# ETH_PHY_IC.net
KiCad netlist of a schematic drawn in Altium Designer
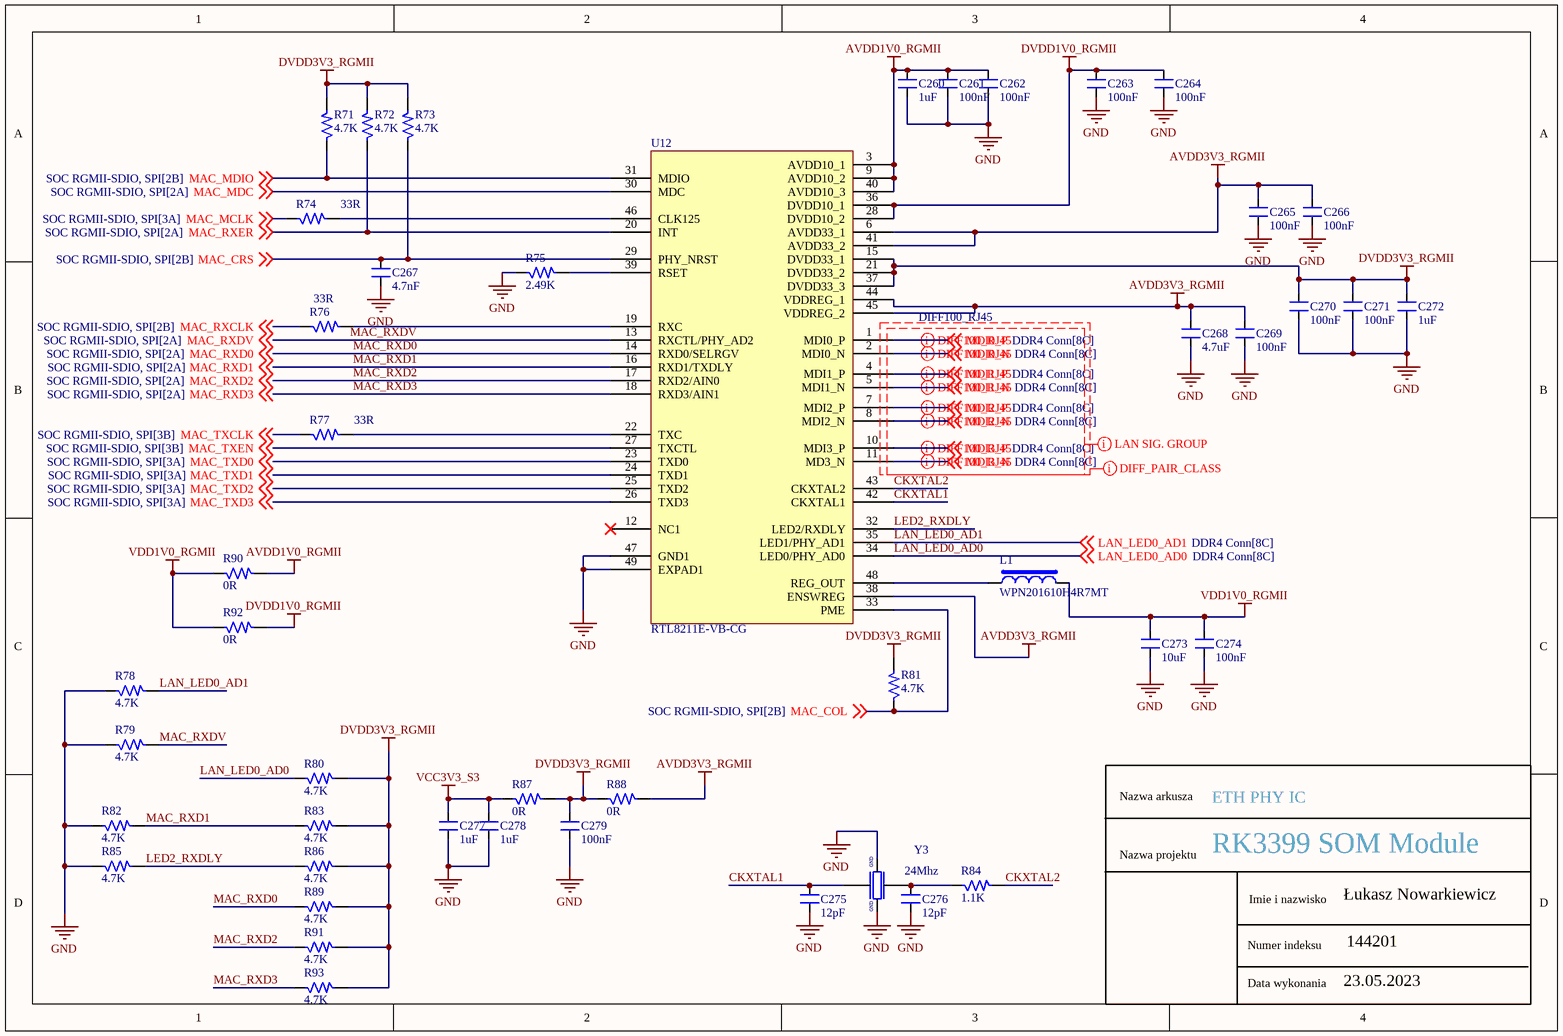
[diagram p0: ETH PHY IC.SchDoc]

(export (version "E")
  (design (tool "Eeschema 10.0.6"))
  (components
    (comp (ref "C260")
      (value "1uF")
      (footprint "CAP_0201")
      (description "1µF ±20% 16V Ceramic Capacitor X5R 0201 (0603 Metric)")
      (fields
        (field (name "MANUFACTURER") "Samsung Electro-Mechanics")
        (field (name "MANUFACTURER PART NUMBER") "CL03A105MO3NRNH")
      )
      (libsource (lib "EsteemPCB_SOM_Course_intlib") (part "CAP_1uF-16V-10%-0201"))
    )
    (comp (ref "C261")
      (value "100nF")
      (footprint "CAP_0201")
      (description "0.1µF ±10% 25V Ceramic Capacitor X5R 0201 (0603 Metric)")
      (fields
        (field (name "MANUFACTURER") "TDK Corporation")
        (field (name "MANUFACTURER PART NUMBER") "C0603X5R1E104K030BB")
      )
      (libsource (lib "EsteemPCB_SOM_Course_intlib") (part "CAP_100nF-25V-10%-0201"))
    )
    (comp (ref "C262")
      (value "100nF")
      (footprint "CAP_0201")
      (description "0.1µF ±10% 25V Ceramic Capacitor X5R 0201 (0603 Metric)")
      (fields
        (field (name "MANUFACTURER") "TDK Corporation")
        (field (name "MANUFACTURER PART NUMBER") "C0603X5R1E104K030BB")
      )
      (libsource (lib "EsteemPCB_SOM_Course_intlib") (part "CAP_100nF-25V-10%-0201"))
    )
    (comp (ref "C263")
      (value "100nF")
      (footprint "CAP_0201")
      (description "0.1µF ±10% 25V Ceramic Capacitor X5R 0201 (0603 Metric)")
      (fields
        (field (name "MANUFACTURER") "TDK Corporation")
        (field (name "MANUFACTURER PART NUMBER") "C0603X5R1E104K030BB")
      )
      (libsource (lib "EsteemPCB_SOM_Course_intlib") (part "CAP_100nF-25V-10%-0201"))
    )
    (comp (ref "C264")
      (value "100nF")
      (footprint "CAP_0201")
      (description "0.1µF ±10% 25V Ceramic Capacitor X5R 0201 (0603 Metric)")
      (fields
        (field (name "MANUFACTURER") "TDK Corporation")
        (field (name "MANUFACTURER PART NUMBER") "C0603X5R1E104K030BB")
      )
      (libsource (lib "EsteemPCB_SOM_Course_intlib") (part "CAP_100nF-25V-10%-0201"))
    )
    (comp (ref "C265")
      (value "100nF")
      (footprint "CAP_0201")
      (description "0.1µF ±10% 25V Ceramic Capacitor X5R 0201 (0603 Metric)")
      (fields
        (field (name "MANUFACTURER") "TDK Corporation")
        (field (name "MANUFACTURER PART NUMBER") "C0603X5R1E104K030BB")
      )
      (libsource (lib "EsteemPCB_SOM_Course_intlib") (part "CAP_100nF-25V-10%-0201"))
    )
    (comp (ref "C266")
      (value "100nF")
      (footprint "CAP_0201")
      (description "0.1µF ±10% 25V Ceramic Capacitor X5R 0201 (0603 Metric)")
      (fields
        (field (name "MANUFACTURER") "TDK Corporation")
        (field (name "MANUFACTURER PART NUMBER") "C0603X5R1E104K030BB")
      )
      (libsource (lib "EsteemPCB_SOM_Course_intlib") (part "CAP_100nF-25V-10%-0201"))
    )
    (comp (ref "C267")
      (value "4.7nF")
      (footprint "CAP_0201")
      (description "4700pF ±10% 10V Ceramic Capacitor X7R 0201 (0603 Metric)")
      (fields
        (field (name "MANUFACTURER") "AVX Corporation")
        (field (name "MANUFACTURER PART NUMBER") "0201ZC472KAT2A")
      )
      (libsource (lib "EsteemPCB_SOM_Course_intlib") (part "CAP_4.7nF-10V-10%-0201"))
    )
    (comp (ref "C268")
      (value "4.7uF")
      (footprint "CAP_0201")
      (description "4.7µF ±20% 6.3V Ceramic Capacitor X5R 0201 (0603 Metric)")
      (fields
        (field (name "MANUFACTURER") "Murata Electronics")
        (field (name "MANUFACTURER PART NUMBER") "GRM035R60J475ME15D")
      )
      (libsource (lib "EsteemPCB_SOM_Course_intlib") (part "CAP_4.7uF-6.3V-20%-0201"))
    )
    (comp (ref "C269")
      (value "100nF")
      (footprint "CAP_0201")
      (description "0.1µF ±10% 25V Ceramic Capacitor X5R 0201 (0603 Metric)")
      (fields
        (field (name "MANUFACTURER") "TDK Corporation")
        (field (name "MANUFACTURER PART NUMBER") "C0603X5R1E104K030BB")
      )
      (libsource (lib "EsteemPCB_SOM_Course_intlib") (part "CAP_100nF-25V-10%-0201"))
    )
    (comp (ref "C270")
      (value "100nF")
      (footprint "CAP_0201")
      (description "0.1µF ±10% 25V Ceramic Capacitor X5R 0201 (0603 Metric)")
      (fields
        (field (name "MANUFACTURER") "TDK Corporation")
        (field (name "MANUFACTURER PART NUMBER") "C0603X5R1E104K030BB")
      )
      (libsource (lib "EsteemPCB_SOM_Course_intlib") (part "CAP_100nF-25V-10%-0201"))
    )
    (comp (ref "C271")
      (value "100nF")
      (footprint "CAP_0201")
      (description "0.1µF ±10% 25V Ceramic Capacitor X5R 0201 (0603 Metric)")
      (fields
        (field (name "MANUFACTURER") "TDK Corporation")
        (field (name "MANUFACTURER PART NUMBER") "C0603X5R1E104K030BB")
      )
      (libsource (lib "EsteemPCB_SOM_Course_intlib") (part "CAP_100nF-25V-10%-0201"))
    )
    (comp (ref "C272")
      (value "1uF")
      (footprint "CAP_0603")
      (description "1µF ±10% 10V Ceramic Capacitor X5R 0603 (1608 Metric)")
      (fields
        (field (name "MANUFACTURER") "Samsung Electro-Mechanics")
        (field (name "MANUFACTURER PART NUMBER") "CL10A105KP8NNNC")
      )
      (libsource (lib "RK3399 _Module_Schlib") (part "CAP_1uF-10V-5%-0603"))
    )
    (comp (ref "C273")
      (value "10uF")
      (footprint "CAP_0402")
      (description "10µF ±20% 10V Ceramic Capacitor X5R 0402 (1005 Metric)")
      (fields
        (field (name "MANUFACTURER PART NUMBER") "CL05A106MP5NUNC")
        (field (name "MANUFACTURER") "Samsung Electro-Mechanics")
      )
      (libsource (lib "EsteemPCB_SOM_Course_intlib") (part "CAP_10uF-10V-20%-0402"))
    )
    (comp (ref "C274")
      (value "100nF")
      (footprint "CAP_0201")
      (description "0.1µF ±10% 25V Ceramic Capacitor X5R 0201 (0603 Metric)")
      (fields
        (field (name "MANUFACTURER") "TDK Corporation")
        (field (name "MANUFACTURER PART NUMBER") "C0603X5R1E104K030BB")
      )
      (libsource (lib "EsteemPCB_SOM_Course_intlib") (part "CAP_100nF-25V-10%-0201"))
    )
    (comp (ref "C275")
      (value "12pF")
      (footprint "CAP_0201")
      (description "12pF ±10% 16V Ceramic Capacitor C0G, NP0 0201 (0603 Metric)")
      (fields
        (field (name "MANUFACTURER") "AVX Corporation")
        (field (name "MANUFACTURER PART NUMBER") "0201YA120KAT2A")
      )
      (libsource (lib "EsteemPCB_SOM_Course_intlib") (part "CAP_12pF-16V-10%-0201"))
    )
    (comp (ref "C276")
      (value "12pF")
      (footprint "CAP_0201")
      (description "12pF ±10% 16V Ceramic Capacitor C0G, NP0 0201 (0603 Metric)")
      (fields
        (field (name "MANUFACTURER") "AVX Corporation")
        (field (name "MANUFACTURER PART NUMBER") "0201YA120KAT2A")
      )
      (libsource (lib "EsteemPCB_SOM_Course_intlib") (part "CAP_12pF-16V-10%-0201"))
    )
    (comp (ref "C277")
      (value "1uF")
      (footprint "CAP_0201")
      (description "1µF ±20% 16V Ceramic Capacitor X5R 0201 (0603 Metric)")
      (fields
        (field (name "MANUFACTURER") "Samsung Electro-Mechanics")
        (field (name "MANUFACTURER PART NUMBER") "CL03A105MO3NRNH")
      )
      (libsource (lib "EsteemPCB_SOM_Course_intlib") (part "CAP_1uF-16V-10%-0201"))
    )
    (comp (ref "C278")
      (value "1uF")
      (footprint "CAP_0201")
      (description "1µF ±20% 16V Ceramic Capacitor X5R 0201 (0603 Metric)")
      (fields
        (field (name "MANUFACTURER") "Samsung Electro-Mechanics")
        (field (name "MANUFACTURER PART NUMBER") "CL03A105MO3NRNH")
      )
      (libsource (lib "EsteemPCB_SOM_Course_intlib") (part "CAP_1uF-16V-10%-0201"))
    )
    (comp (ref "C279")
      (value "100nF")
      (footprint "CAP_0201")
      (description "0.1µF ±10% 25V Ceramic Capacitor X5R 0201 (0603 Metric)")
      (fields
        (field (name "MANUFACTURER") "TDK Corporation")
        (field (name "MANUFACTURER PART NUMBER") "C0603X5R1E104K030BB")
      )
      (libsource (lib "EsteemPCB_SOM_Course_intlib") (part "CAP_100nF-25V-10%-0201"))
    )
    (comp (ref "L1")
      (value "WPN201610H4R7MT")
      (footprint "IND_62.9_110X86.6_SMD")
      (description "4.7uH ±20% 900mA 425mΩ SMD,2.0x1.6x1.0mm Power Inductors RoHS")
      (fields (field (name "MANUFACTURER") "Sunlord"))
      (libsource (lib "RK3399 _Module_Schlib") (part "IND_4.7uH-0.9A-20%-SMD"))
    )
    (comp (ref "R71")
      (value "4.7K")
      (footprint "RES_0201")
      (description "4.02 kOhms ±1% 0.05W, 1/20W Chip Resistor 0201 (0603 Metric) Thick Film")
      (fields
        (field (name "MANUFACTURER") "Yageo")
        (field (name "MANUFACTURER PART NUMBER") "RC0201FR-074K02L")
      )
      (libsource (lib "EsteemPCB_SOM_Course_intlib") (part "RES_4.7K-0.1W-1%-0201"))
    )
    (comp (ref "R72")
      (value "4.7K")
      (footprint "RES_0201")
      (description "4.02 kOhms ±1% 0.05W, 1/20W Chip Resistor 0201 (0603 Metric) Thick Film")
      (fields
        (field (name "MANUFACTURER") "Yageo")
        (field (name "MANUFACTURER PART NUMBER") "RC0201FR-074K02L")
      )
      (libsource (lib "EsteemPCB_SOM_Course_intlib") (part "RES_4.7K-0.1W-1%-0201"))
    )
    (comp (ref "R73")
      (value "4.7K")
      (footprint "RES_0201")
      (description "4.02 kOhms ±1% 0.05W, 1/20W Chip Resistor 0201 (0603 Metric) Thick Film")
      (fields
        (field (name "MANUFACTURER") "Yageo")
        (field (name "MANUFACTURER PART NUMBER") "RC0201FR-074K02L")
      )
      (libsource (lib "EsteemPCB_SOM_Course_intlib") (part "RES_4.7K-0.1W-1%-0201"))
    )
    (comp (ref "R74")
      (value "33R")
      (footprint "RES_0201")
      (description "33 Ohms ±1% 0.05W, 1/20W Chip Resistor 0201 (0603 Metric) Thick Film")
      (fields
        (field (name "MANUFACTURER") "Yageo")
        (field (name "MANUFACTURER PART NUMBER") "RC0201FR-0733RL")
      )
      (libsource (lib "EsteemPCB_SOM_Course_intlib") (part "RES_33R-0.05W-1%-0201"))
    )
    (comp (ref "R75")
      (value "2.49K")
      (footprint "RES_0201")
      (description "2.49 kOhms ±1% 0.05W, 1/20W Chip Resistor 0201 (0603 Metric) Automotive AEC-Q200 Thick Film")
      (fields
        (field (name "MANUFACTURER") "Panasonic Electronic Components")
        (field (name "MANUFACTURER PART NUMBER") "ERJ-1GNF2491C")
      )
      (libsource (lib "EsteemPCB_SOM_Course_intlib") (part "RES_2.49K-0.05W-1%-0201"))
    )
    (comp (ref "R76")
      (value "33R")
      (footprint "RES_0201")
      (description "33 Ohms ±1% 0.05W, 1/20W Chip Resistor 0201 (0603 Metric) Thick Film")
      (fields
        (field (name "MANUFACTURER") "Yageo")
        (field (name "MANUFACTURER PART NUMBER") "RC0201FR-0733RL")
      )
      (libsource (lib "EsteemPCB_SOM_Course_intlib") (part "RES_33R-0.05W-1%-0201"))
    )
    (comp (ref "R77")
      (value "33R")
      (footprint "RES_0201")
      (description "33 Ohms ±1% 0.05W, 1/20W Chip Resistor 0201 (0603 Metric) Thick Film")
      (fields
        (field (name "MANUFACTURER") "Yageo")
        (field (name "MANUFACTURER PART NUMBER") "RC0201FR-0733RL")
      )
      (libsource (lib "EsteemPCB_SOM_Course_intlib") (part "RES_33R-0.05W-1%-0201"))
    )
    (comp (ref "R78")
      (value "4.7K")
      (footprint "RES_0201")
      (description "4.02 kOhms ±1% 0.05W, 1/20W Chip Resistor 0201 (0603 Metric) Thick Film")
      (fields
        (field (name "MANUFACTURER") "Yageo")
        (field (name "MANUFACTURER PART NUMBER") "RC0201FR-074K02L")
      )
      (libsource (lib "EsteemPCB_SOM_Course_intlib") (part "RES_4.7K-0.1W-1%-0201"))
    )
    (comp (ref "R79")
      (value "4.7K")
      (footprint "RES_0201")
      (description "4.02 kOhms ±1% 0.05W, 1/20W Chip Resistor 0201 (0603 Metric) Thick Film")
      (fields
        (field (name "MANUFACTURER") "Yageo")
        (field (name "MANUFACTURER PART NUMBER") "RC0201FR-074K02L")
      )
      (libsource (lib "EsteemPCB_SOM_Course_intlib") (part "RES_4.7K-0.1W-1%-0201"))
    )
    (comp (ref "R80")
      (value "4.7K")
      (footprint "RES_0201")
      (description "4.02 kOhms ±1% 0.05W, 1/20W Chip Resistor 0201 (0603 Metric) Thick Film")
      (fields
        (field (name "MANUFACTURER") "Yageo")
        (field (name "MANUFACTURER PART NUMBER") "RC0201FR-074K02L")
      )
      (libsource (lib "EsteemPCB_SOM_Course_intlib") (part "RES_4.7K-0.1W-1%-0201"))
    )
    (comp (ref "R81")
      (value "4.7K")
      (footprint "RES_0201")
      (description "4.02 kOhms ±1% 0.05W, 1/20W Chip Resistor 0201 (0603 Metric) Thick Film")
      (fields
        (field (name "MANUFACTURER") "Yageo")
        (field (name "MANUFACTURER PART NUMBER") "RC0201FR-074K02L")
      )
      (libsource (lib "EsteemPCB_SOM_Course_intlib") (part "RES_4.7K-0.1W-1%-0201"))
    )
    (comp (ref "R82")
      (value "4.7K")
      (footprint "RES_0201")
      (description "4.02 kOhms ±1% 0.05W, 1/20W Chip Resistor 0201 (0603 Metric) Thick Film")
      (fields
        (field (name "MANUFACTURER") "Yageo")
        (field (name "MANUFACTURER PART NUMBER") "RC0201FR-074K02L")
      )
      (libsource (lib "EsteemPCB_SOM_Course_intlib") (part "RES_4.7K-0.1W-1%-0201"))
    )
    (comp (ref "R83")
      (value "4.7K")
      (footprint "RES_0201")
      (description "4.02 kOhms ±1% 0.05W, 1/20W Chip Resistor 0201 (0603 Metric) Thick Film")
      (fields
        (field (name "MANUFACTURER") "Yageo")
        (field (name "MANUFACTURER PART NUMBER") "RC0201FR-074K02L")
      )
      (libsource (lib "EsteemPCB_SOM_Course_intlib") (part "RES_4.7K-0.1W-1%-0201"))
    )
    (comp (ref "R84")
      (value "1.1K")
      (footprint "RES_0201")
      (description "1.1 kOhms ±1% 0.05W, 1/20W Chip Resistor 0201 (0603 Metric) Automotive AEC-Q200 Thick Film")
      (fields
        (field (name "MANUFACTURER") "Panasonic Electronic Components")
        (field (name "MANUFACTURER PART NUMBER") "ERJ-1GNF1101C")
      )
      (libsource (lib "EsteemPCB_SOM_Course_intlib") (part "RES_1.1K-0.05W-1%-0201"))
    )
    (comp (ref "R85")
      (value "4.7K")
      (footprint "RES_0201")
      (description "4.02 kOhms ±1% 0.05W, 1/20W Chip Resistor 0201 (0603 Metric) Thick Film")
      (fields
        (field (name "MANUFACTURER") "Yageo")
        (field (name "MANUFACTURER PART NUMBER") "RC0201FR-074K02L")
      )
      (libsource (lib "EsteemPCB_SOM_Course_intlib") (part "RES_4.7K-0.1W-1%-0201"))
    )
    (comp (ref "R86")
      (value "4.7K")
      (footprint "RES_0201")
      (description "4.02 kOhms ±1% 0.05W, 1/20W Chip Resistor 0201 (0603 Metric) Thick Film")
      (fields
        (field (name "MANUFACTURER") "Yageo")
        (field (name "MANUFACTURER PART NUMBER") "RC0201FR-074K02L")
      )
      (libsource (lib "EsteemPCB_SOM_Course_intlib") (part "RES_4.7K-0.1W-1%-0201"))
    )
    (comp (ref "R87")
      (value "0R")
      (footprint "RES_0201")
      (description "0 Ohms Jumper 0.05W, 1/20W Chip Resistor 0201 (0603 Metric) Automotive AEC-Q200 Thick Film")
      (fields
        (field (name "MANUFACTURER") "Bourns Inc.")
        (field (name "MANUFACTURER PART NUMBER") "CR0201AJ/-000GLF")
      )
      (libsource (lib "EsteemPCB_SOM_Course_intlib") (part "RES_0R-0.05W-1%-0201"))
    )
    (comp (ref "R88")
      (value "0R")
      (footprint "RES_0201")
      (description "0 Ohms Jumper 0.05W, 1/20W Chip Resistor 0201 (0603 Metric) Automotive AEC-Q200 Thick Film")
      (fields
        (field (name "MANUFACTURER") "Bourns Inc.")
        (field (name "MANUFACTURER PART NUMBER") "CR0201AJ/-000GLF")
      )
      (libsource (lib "EsteemPCB_SOM_Course_intlib") (part "RES_0R-0.05W-1%-0201"))
    )
    (comp (ref "R89")
      (value "4.7K")
      (footprint "RES_0201")
      (description "4.02 kOhms ±1% 0.05W, 1/20W Chip Resistor 0201 (0603 Metric) Thick Film")
      (fields
        (field (name "MANUFACTURER") "Yageo")
        (field (name "MANUFACTURER PART NUMBER") "RC0201FR-074K02L")
      )
      (libsource (lib "EsteemPCB_SOM_Course_intlib") (part "RES_4.7K-0.1W-1%-0201"))
    )
    (comp (ref "R90")
      (value "0R")
      (footprint "RES_0201")
      (description "0 Ohms Jumper 0.05W, 1/20W Chip Resistor 0201 (0603 Metric) Automotive AEC-Q200 Thick Film")
      (fields
        (field (name "MANUFACTURER") "Bourns Inc.")
        (field (name "MANUFACTURER PART NUMBER") "CR0201AJ/-000GLF")
      )
      (libsource (lib "EsteemPCB_SOM_Course_intlib") (part "RES_0R-0.05W-1%-0201"))
    )
    (comp (ref "R91")
      (value "4.7K")
      (footprint "RES_0201")
      (description "4.02 kOhms ±1% 0.05W, 1/20W Chip Resistor 0201 (0603 Metric) Thick Film")
      (fields
        (field (name "MANUFACTURER") "Yageo")
        (field (name "MANUFACTURER PART NUMBER") "RC0201FR-074K02L")
      )
      (libsource (lib "EsteemPCB_SOM_Course_intlib") (part "RES_4.7K-0.1W-1%-0201"))
    )
    (comp (ref "R92")
      (value "0R")
      (footprint "RES_0201")
      (description "0 Ohms Jumper 0.05W, 1/20W Chip Resistor 0201 (0603 Metric) Automotive AEC-Q200 Thick Film")
      (fields
        (field (name "MANUFACTURER") "Bourns Inc.")
        (field (name "MANUFACTURER PART NUMBER") "CR0201AJ/-000GLF")
      )
      (libsource (lib "EsteemPCB_SOM_Course_intlib") (part "RES_0R-0.05W-1%-0201"))
    )
    (comp (ref "R93")
      (value "4.7K")
      (footprint "RES_0201")
      (description "4.02 kOhms ±1% 0.05W, 1/20W Chip Resistor 0201 (0603 Metric) Thick Film")
      (fields
        (field (name "MANUFACTURER") "Yageo")
        (field (name "MANUFACTURER PART NUMBER") "RC0201FR-074K02L")
      )
      (libsource (lib "EsteemPCB_SOM_Course_intlib") (part "RES_4.7K-0.1W-1%-0201"))
    )
    (comp (ref "U12")
      (value "RTL8211E-VB-CG")
      (footprint "QFN48_19.6_324X324_SMD")
      (fields (field (name "MANUFACTURER") "Realtek Semicon"))
      (libsource (lib "RK3399 _Module_Schlib") (part "IC_RTL8211E-VB-CG"))
    )
    (comp (ref "Y3")
      (value "24Mhz")
      (footprint "XTAL_ABM8AIG-24.000MHZ-12-2Z-T3")
      (description "24MHz ±20ppm Crystal 12pF 50 Ohms 4-SMD, No Lead")
      (fields
        (field (name "MANUFACTURER") "Abracon LLC")
        (field (name "MANUFACTURER PART NUMBER") "ABM8AIG-24.000MHZ-12-2Z-T3")
      )
      (libsource (lib "RK3399 _Module_Schlib") (part "XTAL_24Mhz-12pF-4-SMD"))
    )
  )
  (nets
    (net (code "1") (name "/CKXTAL1") (class "Default")
      (node (ref "C275") (pin "2") (pinfunction "2_2") (pintype "passive"))
      (node (ref "U12") (pin "42") (pinfunction "CKXTAL1_42") (pintype "passive"))
      (node (ref "Y3") (pin "1") (pinfunction "1_1") (pintype "passive"))
    )
    (net (code "2") (name "/CKXTAL2") (class "Default")
      (node (ref "R84") (pin "2") (pinfunction "2_2") (pintype "passive"))
      (node (ref "U12") (pin "43") (pinfunction "CKXTAL2_43") (pintype "passive"))
    )
    (net (code "3") (name "/LED2_RXDLY") (class "Default")
      (node (ref "R85") (pin "2") (pinfunction "2_2") (pintype "passive"))
      (node (ref "R86") (pin "1") (pinfunction "1_1") (pintype "passive"))
      (node (ref "U12") (pin "32") (pinfunction "LED2/RXDLY_32") (pintype "passive"))
    )
    (net (code "4") (name "AVDD1V0_RGMII") (class "Default")
      (node (ref "C260") (pin "2") (pinfunction "2_2") (pintype "passive"))
      (node (ref "C261") (pin "2") (pinfunction "2_2") (pintype "passive"))
      (node (ref "C262") (pin "2") (pinfunction "2_2") (pintype "passive"))
      (node (ref "R90") (pin "2") (pinfunction "2_2") (pintype "passive"))
      (node (ref "U12") (pin "3") (pinfunction "AVDD10_1_3") (pintype "passive"))
      (node (ref "U12") (pin "40") (pinfunction "AVDD10_3_40") (pintype "passive"))
      (node (ref "U12") (pin "9") (pinfunction "AVDD10_2_9") (pintype "passive"))
    )
    (net (code "5") (name "AVDD3V3_RGMII") (class "Default")
      (node (ref "C265") (pin "2") (pinfunction "2_2") (pintype "passive"))
      (node (ref "C266") (pin "2") (pinfunction "2_2") (pintype "passive"))
      (node (ref "C268") (pin "2") (pinfunction "2_2") (pintype "passive"))
      (node (ref "C269") (pin "2") (pinfunction "2_2") (pintype "passive"))
      (node (ref "R88") (pin "2") (pinfunction "2_2") (pintype "passive"))
      (node (ref "U12") (pin "38") (pinfunction "ENSWREG_38") (pintype "passive"))
      (node (ref "U12") (pin "41") (pinfunction "AVDD33_2_41") (pintype "passive"))
      (node (ref "U12") (pin "44") (pinfunction "VDDREG_1_44") (pintype "passive"))
      (node (ref "U12") (pin "45") (pinfunction "VDDREG_2_45") (pintype "passive"))
      (node (ref "U12") (pin "6") (pinfunction "AVDD33_1_6") (pintype "passive"))
    )
    (net (code "6") (name "DVDD1V0_RGMII") (class "Default")
      (node (ref "C263") (pin "2") (pinfunction "2_2") (pintype "passive"))
      (node (ref "C264") (pin "2") (pinfunction "2_2") (pintype "passive"))
      (node (ref "R92") (pin "2") (pinfunction "2_2") (pintype "passive"))
      (node (ref "U12") (pin "28") (pinfunction "DVDD10_2_28") (pintype "passive"))
      (node (ref "U12") (pin "36") (pinfunction "DVDD10_1_36") (pintype "passive"))
    )
    (net (code "7") (name "DVDD3V3_RGMII") (class "Default")
      (node (ref "C270") (pin "2") (pinfunction "2_2") (pintype "passive"))
      (node (ref "C271") (pin "2") (pinfunction "2_2") (pintype "passive"))
      (node (ref "C272") (pin "2") (pinfunction "2_2") (pintype "passive"))
      (node (ref "C279") (pin "2") (pinfunction "2_2") (pintype "passive"))
      (node (ref "R71") (pin "2") (pinfunction "2_2") (pintype "passive"))
      (node (ref "R72") (pin "2") (pinfunction "2_2") (pintype "passive"))
      (node (ref "R73") (pin "2") (pinfunction "2_2") (pintype "passive"))
      (node (ref "R80") (pin "2") (pinfunction "2_2") (pintype "passive"))
      (node (ref "R81") (pin "2") (pinfunction "2_2") (pintype "passive"))
      (node (ref "R83") (pin "2") (pinfunction "2_2") (pintype "passive"))
      (node (ref "R86") (pin "2") (pinfunction "2_2") (pintype "passive"))
      (node (ref "R87") (pin "2") (pinfunction "2_2") (pintype "passive"))
      (node (ref "R88") (pin "1") (pinfunction "1_1") (pintype "passive"))
      (node (ref "R89") (pin "2") (pinfunction "2_2") (pintype "passive"))
      (node (ref "R91") (pin "2") (pinfunction "2_2") (pintype "passive"))
      (node (ref "R93") (pin "2") (pinfunction "2_2") (pintype "passive"))
      (node (ref "U12") (pin "15") (pinfunction "DVDD33_1_15") (pintype "passive"))
      (node (ref "U12") (pin "21") (pinfunction "DVDD33_2_21") (pintype "passive"))
      (node (ref "U12") (pin "37") (pinfunction "DVDD33_3_37") (pintype "passive"))
    )
    (net (code "8") (name "GND") (class "Default")
      (node (ref "C260") (pin "1") (pinfunction "1_1") (pintype "passive"))
      (node (ref "C261") (pin "1") (pinfunction "1_1") (pintype "passive"))
      (node (ref "C262") (pin "1") (pinfunction "1_1") (pintype "passive"))
      (node (ref "C263") (pin "1") (pinfunction "1_1") (pintype "passive"))
      (node (ref "C264") (pin "1") (pinfunction "1_1") (pintype "passive"))
      (node (ref "C265") (pin "1") (pinfunction "1_1") (pintype "passive"))
      (node (ref "C266") (pin "1") (pinfunction "1_1") (pintype "passive"))
      (node (ref "C267") (pin "1") (pinfunction "1_1") (pintype "passive"))
      (node (ref "C268") (pin "1") (pinfunction "1_1") (pintype "passive"))
      (node (ref "C269") (pin "1") (pinfunction "1_1") (pintype "passive"))
      (node (ref "C270") (pin "1") (pinfunction "1_1") (pintype "passive"))
      (node (ref "C271") (pin "1") (pinfunction "1_1") (pintype "passive"))
      (node (ref "C272") (pin "1") (pinfunction "1_1") (pintype "passive"))
      (node (ref "C273") (pin "1") (pinfunction "1_1") (pintype "passive"))
      (node (ref "C274") (pin "1") (pinfunction "1_1") (pintype "passive"))
      (node (ref "C275") (pin "1") (pinfunction "1_1") (pintype "passive"))
      (node (ref "C276") (pin "1") (pinfunction "1_1") (pintype "passive"))
      (node (ref "C277") (pin "1") (pinfunction "1_1") (pintype "passive"))
      (node (ref "C278") (pin "1") (pinfunction "1_1") (pintype "passive"))
      (node (ref "C279") (pin "1") (pinfunction "1_1") (pintype "passive"))
      (node (ref "R75") (pin "1") (pinfunction "1_1") (pintype "passive"))
      (node (ref "R78") (pin "1") (pinfunction "1_1") (pintype "passive"))
      (node (ref "R79") (pin "1") (pinfunction "1_1") (pintype "passive"))
      (node (ref "R82") (pin "1") (pinfunction "1_1") (pintype "passive"))
      (node (ref "R85") (pin "1") (pinfunction "1_1") (pintype "passive"))
      (node (ref "U12") (pin "47") (pinfunction "GND1_47") (pintype "passive"))
      (node (ref "U12") (pin "49") (pinfunction "EXPAD1_49") (pintype "passive"))
      (node (ref "Y3") (pin "2") (pinfunction "2_2") (pintype "passive"))
      (node (ref "Y3") (pin "4") (pinfunction "4_4") (pintype "passive"))
    )
    (net (code "9") (name "LAN_LED0_AD0") (class "Default")
      (node (ref "R80") (pin "1") (pinfunction "1_1") (pintype "passive"))
      (node (ref "U12") (pin "34") (pinfunction "LED0/PHY_AD0_34") (pintype "passive"))
    )
    (net (code "10") (name "LAN_LED0_AD1") (class "Default")
      (node (ref "R78") (pin "2") (pinfunction "2_2") (pintype "passive"))
      (node (ref "U12") (pin "35") (pinfunction "LED1/PHY_AD1_35") (pintype "passive"))
    )
    (net (code "11") (name "MAC_COL") (class "Default")
      (node (ref "R81") (pin "1") (pinfunction "1_1") (pintype "passive"))
      (node (ref "U12") (pin "33") (pinfunction "PME_33") (pintype "passive"))
    )
    (net (code "12") (name "MAC_CRS") (class "Default")
      (node (ref "C267") (pin "2") (pinfunction "2_2") (pintype "passive"))
      (node (ref "R73") (pin "1") (pinfunction "1_1") (pintype "passive"))
      (node (ref "U12") (pin "29") (pinfunction "PHY_NRST_29") (pintype "passive"))
    )
    (net (code "13") (name "MAC_MCLK") (class "Default")
      (node (ref "R74") (pin "1") (pinfunction "1_1") (pintype "passive"))
    )
    (net (code "14") (name "MAC_MDC") (class "Default")
      (node (ref "U12") (pin "30") (pinfunction "MDC_30") (pintype "passive"))
    )
    (net (code "15") (name "MAC_MDIO") (class "Default")
      (node (ref "R71") (pin "1") (pinfunction "1_1") (pintype "passive"))
      (node (ref "U12") (pin "31") (pinfunction "MDIO_31") (pintype "passive"))
    )
    (net (code "16") (name "MAC_RXCLK") (class "Default")
      (node (ref "R76") (pin "1") (pinfunction "1_1") (pintype "passive"))
    )
    (net (code "17") (name "MAC_RXD0") (class "Default")
      (node (ref "R89") (pin "1") (pinfunction "1_1") (pintype "passive"))
      (node (ref "U12") (pin "14") (pinfunction "RXD0/SELRGV_14") (pintype "passive"))
    )
    (net (code "18") (name "MAC_RXD1") (class "Default")
      (node (ref "R82") (pin "2") (pinfunction "2_2") (pintype "passive"))
      (node (ref "R83") (pin "1") (pinfunction "1_1") (pintype "passive"))
      (node (ref "U12") (pin "16") (pinfunction "RXD1/TXDLY_16") (pintype "passive"))
    )
    (net (code "19") (name "MAC_RXD2") (class "Default")
      (node (ref "R91") (pin "1") (pinfunction "1_1") (pintype "passive"))
      (node (ref "U12") (pin "17") (pinfunction "RXD2/AIN0_17") (pintype "passive"))
    )
    (net (code "20") (name "MAC_RXD3") (class "Default")
      (node (ref "R93") (pin "1") (pinfunction "1_1") (pintype "passive"))
      (node (ref "U12") (pin "18") (pinfunction "RXD3/AIN1_18") (pintype "passive"))
    )
    (net (code "21") (name "MAC_RXDV") (class "Default")
      (node (ref "R79") (pin "2") (pinfunction "2_2") (pintype "passive"))
      (node (ref "U12") (pin "13") (pinfunction "RXCTL/PHY_AD2_13") (pintype "passive"))
    )
    (net (code "22") (name "MAC_RXER") (class "Default")
      (node (ref "R72") (pin "1") (pinfunction "1_1") (pintype "passive"))
      (node (ref "U12") (pin "20") (pinfunction "INT_20") (pintype "passive"))
    )
    (net (code "23") (name "MAC_TXCLK") (class "Default")
      (node (ref "R77") (pin "1") (pinfunction "1_1") (pintype "passive"))
    )
    (net (code "24") (name "MAC_TXD0") (class "Default")
      (node (ref "U12") (pin "23") (pinfunction "TXD0_23") (pintype "passive"))
    )
    (net (code "25") (name "MAC_TXD1") (class "Default")
      (node (ref "U12") (pin "24") (pinfunction "TXD1_24") (pintype "passive"))
    )
    (net (code "26") (name "MAC_TXD2") (class "Default")
      (node (ref "U12") (pin "25") (pinfunction "TXD2_25") (pintype "passive"))
    )
    (net (code "27") (name "MAC_TXD3") (class "Default")
      (node (ref "U12") (pin "26") (pinfunction "TXD3_26") (pintype "passive"))
    )
    (net (code "28") (name "MAC_TXEN") (class "Default")
      (node (ref "U12") (pin "27") (pinfunction "TXCTL_27") (pintype "passive"))
    )
    (net (code "29") (name "MDI0_N") (class "Default")
      (node (ref "U12") (pin "2") (pinfunction "MDI0_N_2") (pintype "passive"))
    )
    (net (code "30") (name "MDI0_P") (class "Default")
      (node (ref "U12") (pin "1") (pinfunction "MDI0_P_1") (pintype "passive"))
    )
    (net (code "31") (name "MDI1_N") (class "Default")
      (node (ref "U12") (pin "5") (pinfunction "MDI1_N_5") (pintype "passive"))
    )
    (net (code "32") (name "MDI1_P") (class "Default")
      (node (ref "U12") (pin "4") (pinfunction "MDI1_P_4") (pintype "passive"))
    )
    (net (code "33") (name "MDI2_N") (class "Default")
      (node (ref "U12") (pin "8") (pinfunction "MDI2_N_8") (pintype "passive"))
    )
    (net (code "34") (name "MDI2_P") (class "Default")
      (node (ref "U12") (pin "7") (pinfunction "MDI2_P_7") (pintype "passive"))
    )
    (net (code "35") (name "MDI3_N") (class "Default")
      (node (ref "U12") (pin "11") (pinfunction "MD3_N_11") (pintype "passive"))
    )
    (net (code "36") (name "MDI3_P") (class "Default")
      (node (ref "U12") (pin "10") (pinfunction "MDI3_P_10") (pintype "passive"))
    )
    (net (code "37") (name "Net-(C276-Pad2)") (class "Default")
      (node (ref "C276") (pin "2") (pinfunction "2_2") (pintype "passive"))
      (node (ref "R84") (pin "1") (pinfunction "1_1") (pintype "passive"))
      (node (ref "Y3") (pin "3") (pinfunction "3_3") (pintype "passive"))
    )
    (net (code "38") (name "Net-(U12-CLK125)") (class "Default")
      (node (ref "R74") (pin "2") (pinfunction "2_2") (pintype "passive"))
      (node (ref "U12") (pin "46") (pinfunction "CLK125_46") (pintype "passive"))
    )
    (net (code "39") (name "Net-(U12-REG_OUT)") (class "Default")
      (node (ref "L1") (pin "1") (pinfunction "1_1") (pintype "passive"))
      (node (ref "U12") (pin "48") (pinfunction "REG_OUT_48") (pintype "passive"))
    )
    (net (code "40") (name "Net-(U12-RSET)") (class "Default")
      (node (ref "R75") (pin "2") (pinfunction "2_2") (pintype "passive"))
      (node (ref "U12") (pin "39") (pinfunction "RSET_39") (pintype "passive"))
    )
    (net (code "41") (name "Net-(U12-RXC)") (class "Default")
      (node (ref "R76") (pin "2") (pinfunction "2_2") (pintype "passive"))
      (node (ref "U12") (pin "19") (pinfunction "RXC_19") (pintype "passive"))
    )
    (net (code "42") (name "Net-(U12-TXC)") (class "Default")
      (node (ref "R77") (pin "2") (pinfunction "2_2") (pintype "passive"))
      (node (ref "U12") (pin "22") (pinfunction "TXC_22") (pintype "passive"))
    )
    (net (code "43") (name "VCC3V3_S3") (class "Default")
      (node (ref "C277") (pin "2") (pinfunction "2_2") (pintype "passive"))
      (node (ref "C278") (pin "2") (pinfunction "2_2") (pintype "passive"))
      (node (ref "R87") (pin "1") (pinfunction "1_1") (pintype "passive"))
    )
    (net (code "44") (name "VDD1V0_RGMII") (class "Default")
      (node (ref "C273") (pin "2") (pinfunction "2_2") (pintype "passive"))
      (node (ref "C274") (pin "2") (pinfunction "2_2") (pintype "passive"))
      (node (ref "L1") (pin "2") (pinfunction "2_2") (pintype "passive"))
      (node (ref "R90") (pin "1") (pinfunction "1_1") (pintype "passive"))
      (node (ref "R92") (pin "1") (pinfunction "1_1") (pintype "passive"))
    )
    (net (code "45") (name "unconnected-(U12-NC1-Pad12)") (class "Default")
      (node (ref "U12") (pin "12") (pinfunction "NC1_12") (pintype "passive+no_connect"))
    )
  )
)
